# PulseGenerator.net
KiCad netlist of a schematic drawn in EAGLE
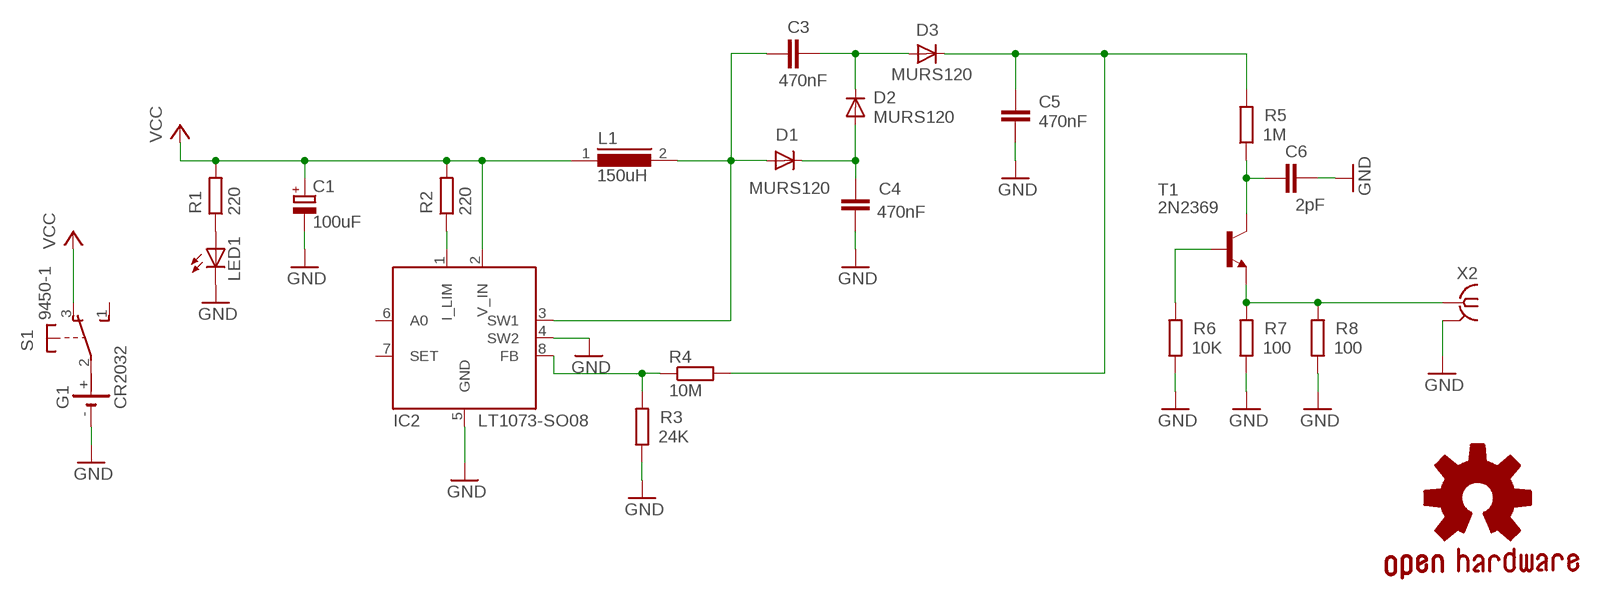
[diagram p0: schematic, sheet 1]

(export (version "E")
  (design (tool "Eeschema 10.0.6"))
  (components
    (comp (ref "C1")
      (value "100uF")
      (footprint "eagle-import:D_7343-31R")
      (libsource (lib "eagle-import") (part "CPOL-EUD/7343-31R"))
    )
    (comp (ref "C3")
      (value "470nF")
      (footprint "eagle-import:C1206")
      (libsource (lib "eagle-import") (part "C-EUC1206"))
    )
    (comp (ref "C4")
      (value "470nF")
      (footprint "eagle-import:C1206")
      (libsource (lib "eagle-import") (part "C-EUC1206"))
    )
    (comp (ref "C5")
      (value "470nF")
      (footprint "eagle-import:C1206")
      (libsource (lib "eagle-import") (part "C-EUC1206"))
    )
    (comp (ref "C6")
      (value "2pF")
      (footprint "eagle-import:C1206")
      (libsource (lib "eagle-import") (part "C-EUC1206"))
    )
    (comp (ref "D1")
      (value "MURS120")
      (footprint "eagle-import:DO214AA")
      (libsource (lib "eagle-import") (part "DIODE-DO214AA"))
    )
    (comp (ref "D2")
      (value "MURS120")
      (footprint "eagle-import:DO214AA")
      (libsource (lib "eagle-import") (part "DIODE-DO214AA"))
    )
    (comp (ref "D3")
      (value "MURS120")
      (footprint "eagle-import:DO214AA")
      (libsource (lib "eagle-import") (part "DIODE-DO214AA"))
    )
    (comp (ref "G1")
      (value "CR2032")
      (footprint "eagle-import:CR2032SMD")
      (libsource (lib "eagle-import") (part "CR2032"))
    )
    (comp (ref "GOLD_ORB_SM1")
      (value "OSHWLOGO_GOLD_ORB_SM")
      (footprint "eagle-import:OSHW2")
      (libsource (lib "eagle-import") (part "OSHWLOGO_GOLD_ORB_SM"))
    )
    (comp (ref "IC2")
      (value "LT1073-SO08")
      (footprint "eagle-import:SO08")
      (libsource (lib "eagle-import") (part "LT1073-SO08"))
    )
    (comp (ref "L1")
      (value "150uH")
      (footprint "eagle-import:DR125")
      (libsource (lib "eagle-import") (part "DR125"))
    )
    (comp (ref "LED1")
      (value "LEDCHIPLED_1206")
      (footprint "eagle-import:CHIPLED_1206")
      (libsource (lib "eagle-import") (part "LEDCHIPLED_1206"))
    )
    (comp (ref "R1")
      (value "220")
      (footprint "eagle-import:R1206")
      (libsource (lib "eagle-import") (part "R-EU_R1206"))
    )
    (comp (ref "R2")
      (value "220")
      (footprint "eagle-import:R1206")
      (libsource (lib "eagle-import") (part "R-EU_R1206"))
    )
    (comp (ref "R3")
      (value "24K")
      (footprint "eagle-import:R1206")
      (libsource (lib "eagle-import") (part "R-EU_R1206"))
    )
    (comp (ref "R4")
      (value "10M")
      (footprint "eagle-import:R1206")
      (libsource (lib "eagle-import") (part "R-EU_R1206"))
    )
    (comp (ref "R5")
      (value "1M")
      (footprint "eagle-import:R1206")
      (libsource (lib "eagle-import") (part "R-EU_R1206"))
    )
    (comp (ref "R6")
      (value "10K")
      (footprint "eagle-import:R1206")
      (libsource (lib "eagle-import") (part "R-EU_R1206"))
    )
    (comp (ref "R7")
      (value "100")
      (footprint "eagle-import:R1206")
      (libsource (lib "eagle-import") (part "R-EU_R1206"))
    )
    (comp (ref "R8")
      (value "100")
      (footprint "eagle-import:R1206")
      (libsource (lib "eagle-import") (part "R-EU_R1206"))
    )
    (comp (ref "S1")
      (value "9450-1")
      (footprint "eagle-import:9450-1")
      (libsource (lib "eagle-import") (part "9450-1"))
    )
    (comp (ref "T1")
      (value "2N2369")
      (footprint "eagle-import:TO18")
      (libsource (lib "eagle-import") (part "2N2369"))
    )
    (comp (ref "X2")
      (value "BU-SMA-H")
      (footprint "eagle-import:BU-SMA-H")
      (libsource (lib "eagle-import") (part "BU-SMA-H"))
    )
  )
  (nets
    (net (code "1") (name "GND") (class "Default")
      (node (ref "C1") (pin "-") (pinfunction "-_-") (pintype "passive"))
      (node (ref "C4") (pin "2") (pinfunction "2_2") (pintype "passive"))
      (node (ref "C5") (pin "2") (pinfunction "2_2") (pintype "passive"))
      (node (ref "C6") (pin "1") (pinfunction "1_1") (pintype "passive"))
      (node (ref "G1") (pin "-") (pinfunction "-_-") (pintype "passive"))
      (node (ref "IC2") (pin "4") (pinfunction "SW2_4") (pintype "bidirectional"))
      (node (ref "IC2") (pin "5") (pinfunction "GND_5") (pintype "bidirectional"))
      (node (ref "LED1") (pin "C") (pinfunction "C_C") (pintype "passive"))
      (node (ref "R3") (pin "1") (pinfunction "1_1") (pintype "passive"))
      (node (ref "R6") (pin "1") (pinfunction "1_1") (pintype "passive"))
      (node (ref "R7") (pin "1") (pinfunction "1_1") (pintype "passive"))
      (node (ref "R8") (pin "1") (pinfunction "1_1") (pintype "passive"))
      (node (ref "X2") (pin "2") (pinfunction "GND_2") (pintype "power_in"))
    )
    (net (code "2") (name "Net-(C3-Pad1)") (class "Default")
      (node (ref "C3") (pin "1") (pinfunction "1_1") (pintype "passive"))
      (node (ref "D2") (pin "C") (pinfunction "C_C") (pintype "passive"))
      (node (ref "D3") (pin "A") (pinfunction "A_A") (pintype "passive"))
    )
    (net (code "3") (name "Net-(C4-Pad1)") (class "Default")
      (node (ref "C4") (pin "1") (pinfunction "1_1") (pintype "passive"))
      (node (ref "D1") (pin "C") (pinfunction "C_C") (pintype "passive"))
      (node (ref "D2") (pin "A") (pinfunction "A_A") (pintype "passive"))
    )
    (net (code "4") (name "Net-(C5-Pad1)") (class "Default")
      (node (ref "C5") (pin "1") (pinfunction "1_1") (pintype "passive"))
      (node (ref "D3") (pin "C") (pinfunction "C_C") (pintype "passive"))
      (node (ref "R4") (pin "2") (pinfunction "2_2") (pintype "passive"))
      (node (ref "R5") (pin "2") (pinfunction "2_2") (pintype "passive"))
    )
    (net (code "5") (name "Net-(IC2-FB)") (class "Default")
      (node (ref "IC2") (pin "8") (pinfunction "FB_8") (pintype "bidirectional"))
      (node (ref "R3") (pin "2") (pinfunction "2_2") (pintype "passive"))
      (node (ref "R4") (pin "1") (pinfunction "1_1") (pintype "passive"))
    )
    (net (code "6") (name "Net-(IC2-I_LIM)") (class "Default")
      (node (ref "IC2") (pin "1") (pinfunction "I_LIM_1") (pintype "bidirectional"))
      (node (ref "R2") (pin "1") (pinfunction "1_1") (pintype "passive"))
    )
    (net (code "7") (name "Net-(IC2-SW1)") (class "Default")
      (node (ref "C3") (pin "2") (pinfunction "2_2") (pintype "passive"))
      (node (ref "D1") (pin "A") (pinfunction "A_A") (pintype "passive"))
      (node (ref "IC2") (pin "3") (pinfunction "SW1_3") (pintype "bidirectional"))
      (node (ref "L1") (pin "2") (pinfunction "2_2") (pintype "passive"))
    )
    (net (code "8") (name "Net-(LED1-PadA)") (class "Default")
      (node (ref "LED1") (pin "A") (pinfunction "A_A") (pintype "passive"))
      (node (ref "R1") (pin "1") (pinfunction "1_1") (pintype "passive"))
    )
    (net (code "9") (name "Net-(S1-P)") (class "Default")
      (node (ref "G1") (pin "+") (pinfunction "+_+") (pintype "passive"))
      (node (ref "S1") (pin "2") (pinfunction "P_2") (pintype "passive"))
    )
    (net (code "10") (name "Net-(T1-B)") (class "Default")
      (node (ref "R6") (pin "2") (pinfunction "2_2") (pintype "passive"))
      (node (ref "T1") (pin "2") (pinfunction "B_2") (pintype "passive"))
    )
    (net (code "11") (name "Net-(T1-C)") (class "Default")
      (node (ref "C6") (pin "2") (pinfunction "2_2") (pintype "passive"))
      (node (ref "R5") (pin "1") (pinfunction "1_1") (pintype "passive"))
      (node (ref "T1") (pin "3") (pinfunction "C_3") (pintype "passive"))
    )
    (net (code "12") (name "Net-(T1-E)") (class "Default")
      (node (ref "R7") (pin "2") (pinfunction "2_2") (pintype "passive"))
      (node (ref "R8") (pin "2") (pinfunction "2_2") (pintype "passive"))
      (node (ref "T1") (pin "1") (pinfunction "E_1") (pintype "passive"))
      (node (ref "X2") (pin "1") (pinfunction "1_1") (pintype "passive"))
    )
    (net (code "13") (name "VCC") (class "Default")
      (node (ref "C1") (pin "+") (pinfunction "+_+") (pintype "passive"))
      (node (ref "IC2") (pin "2") (pinfunction "V_IN_2") (pintype "bidirectional"))
      (node (ref "L1") (pin "1") (pinfunction "1_1") (pintype "passive"))
      (node (ref "R1") (pin "2") (pinfunction "2_2") (pintype "passive"))
      (node (ref "R2") (pin "2") (pinfunction "2_2") (pintype "passive"))
      (node (ref "S1") (pin "3") (pinfunction "O_3") (pintype "passive"))
    )
    (net (code "14") (name "unconnected-(IC2-A0-Pad6)") (class "Default")
      (node (ref "IC2") (pin "6") (pinfunction "A0_6") (pintype "bidirectional"))
    )
    (net (code "15") (name "unconnected-(IC2-SET-Pad7)") (class "Default")
      (node (ref "IC2") (pin "7") (pinfunction "SET_7") (pintype "bidirectional"))
    )
    (net (code "16") (name "unconnected-(S1-S-Pad1)") (class "Default")
      (node (ref "S1") (pin "1") (pinfunction "S_1") (pintype "passive"))
    )
  )
)
